# Main_Board_SW.net
KiCad netlist of a schematic drawn in EAGLE
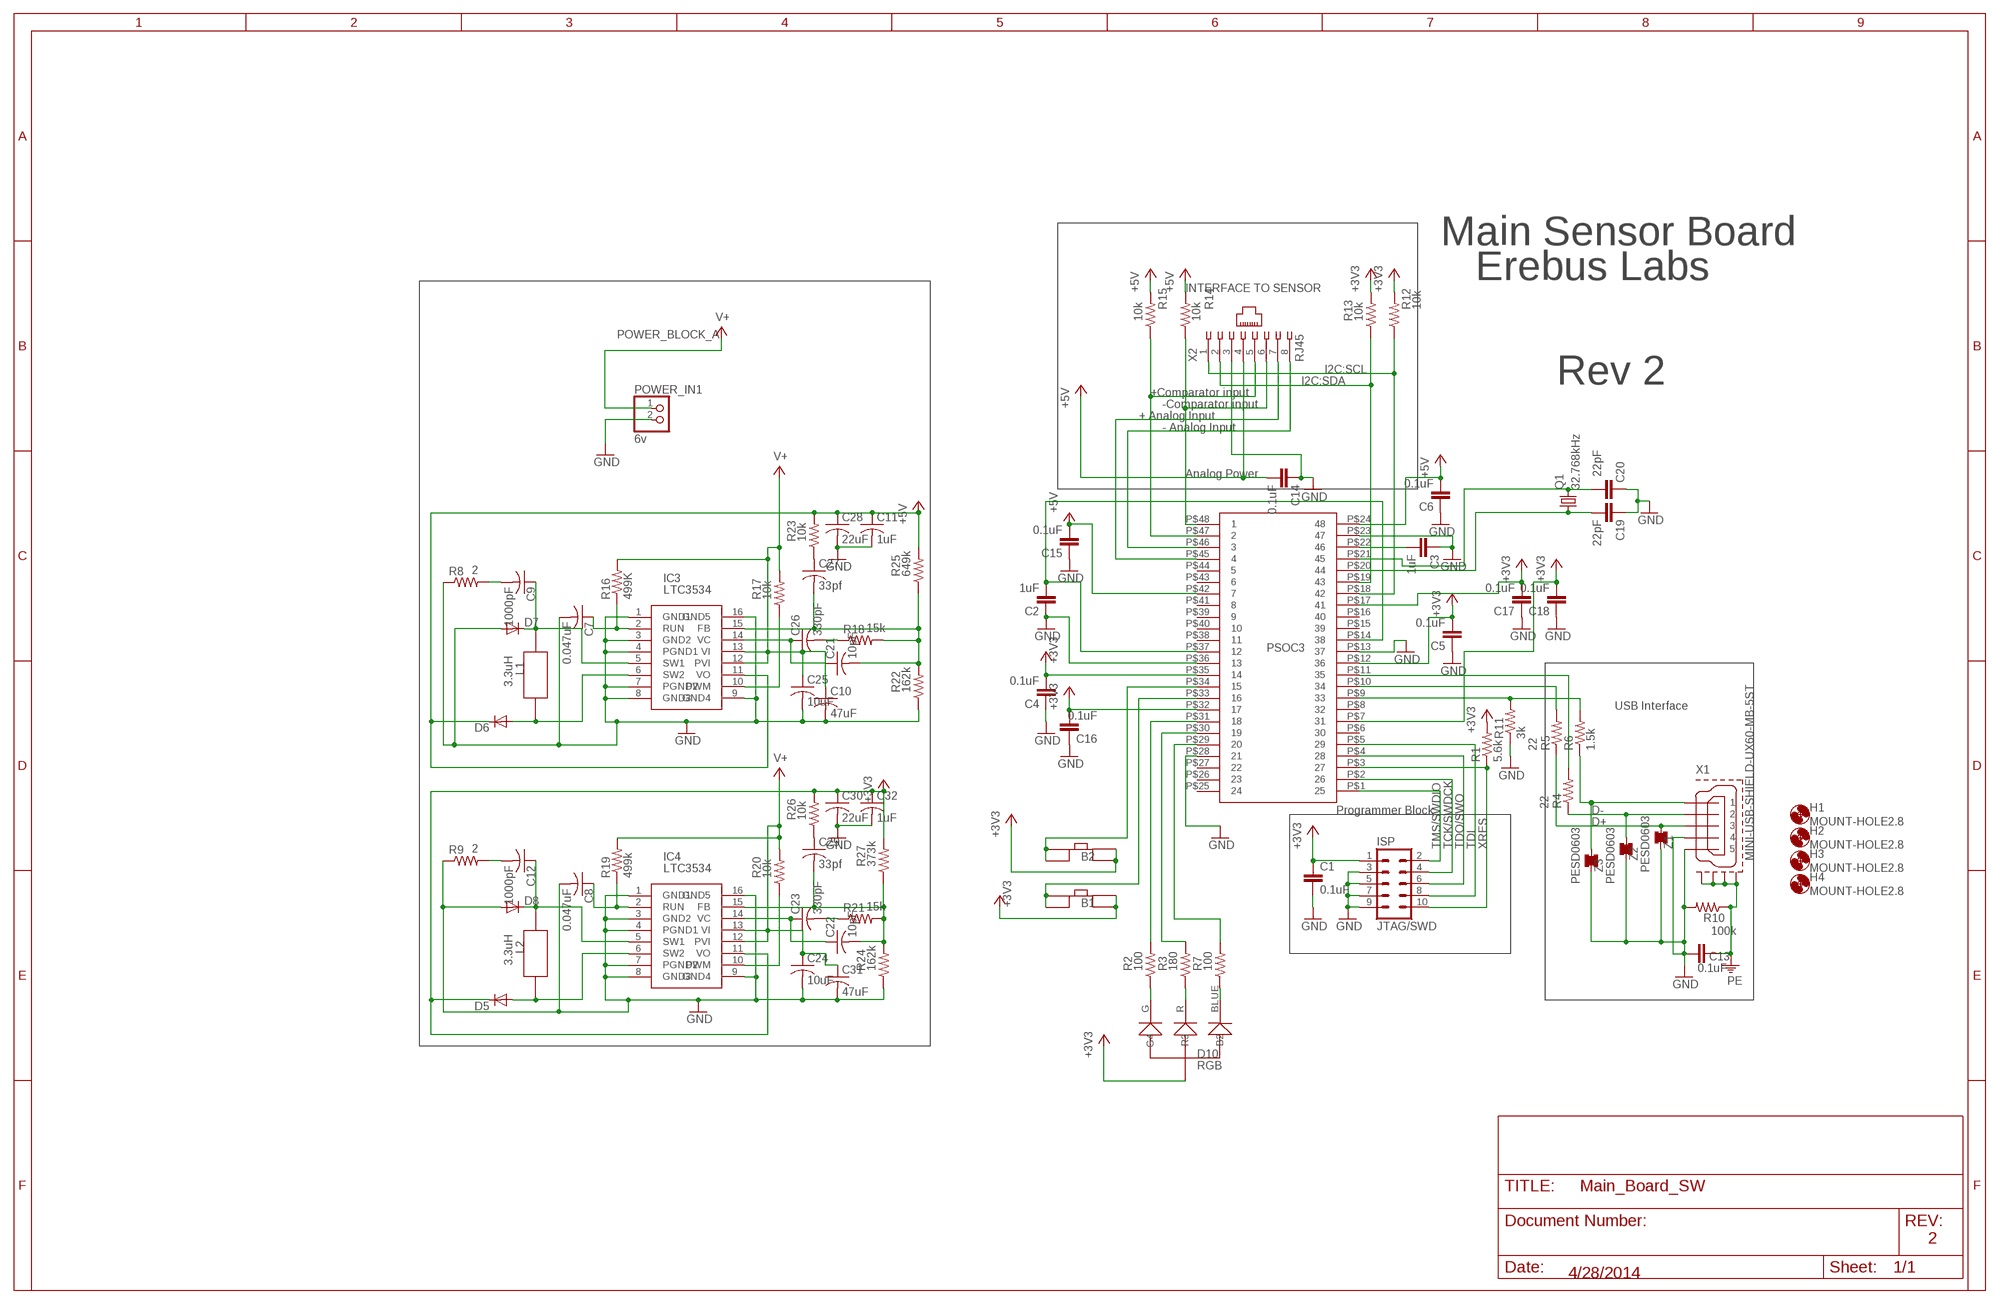
[diagram p0: schematic, sheet 1]

(export (version "E")
  (design (tool "Eeschema 10.0.6"))
  (components
    (comp (ref "C1")
      (value "0.1uF")
      (footprint "eagle-import:C0603K")
      (libsource (lib "eagle-import") (part "C-EUC0603K"))
    )
    (comp (ref "C2")
      (value "1uF")
      (footprint "eagle-import:C0603")
      (libsource (lib "eagle-import") (part "C-EUC0603"))
    )
    (comp (ref "C3")
      (value "1uF")
      (footprint "eagle-import:C0603")
      (libsource (lib "eagle-import") (part "C-EUC0603"))
    )
    (comp (ref "C4")
      (value "0.1uF")
      (footprint "eagle-import:C0603K")
      (libsource (lib "eagle-import") (part "C-EUC0603K"))
    )
    (comp (ref "C5")
      (value "0.1uF")
      (footprint "eagle-import:C0603K")
      (libsource (lib "eagle-import") (part "C-EUC0603K"))
    )
    (comp (ref "C6")
      (value "0.1uF")
      (footprint "eagle-import:C0603K")
      (libsource (lib "eagle-import") (part "C-EUC0603K"))
    )
    (comp (ref "C7")
      (value "0.047uF")
      (footprint "eagle-import:C0402")
      (libsource (lib "eagle-import") (part "C-USC0402"))
    )
    (comp (ref "C8")
      (value "0.047uF")
      (footprint "eagle-import:C0402")
      (libsource (lib "eagle-import") (part "C-USC0402"))
    )
    (comp (ref "C9")
      (value "1000pF")
      (footprint "eagle-import:C0402")
      (libsource (lib "eagle-import") (part "C-USC0402"))
    )
    (comp (ref "C10")
      (value "47uF")
      (footprint "eagle-import:C1210")
      (libsource (lib "eagle-import") (part "C-USC1210"))
    )
    (comp (ref "C11")
      (value "1uF")
      (footprint "eagle-import:C0603")
      (libsource (lib "eagle-import") (part "C-USC0603"))
    )
    (comp (ref "C12")
      (value "1000pF")
      (footprint "eagle-import:C0402")
      (libsource (lib "eagle-import") (part "C-USC0402"))
    )
    (comp (ref "C13")
      (value "0.1uF")
      (footprint "eagle-import:C0603K")
      (libsource (lib "eagle-import") (part "C-EUC0603K"))
    )
    (comp (ref "C14")
      (value "0.1uF")
      (footprint "eagle-import:C0603K")
      (libsource (lib "eagle-import") (part "C-EUC0603K"))
    )
    (comp (ref "C15")
      (value "0.1uF")
      (footprint "eagle-import:C0603K")
      (libsource (lib "eagle-import") (part "C-EUC0603K"))
    )
    (comp (ref "C16")
      (value "0.1uF")
      (footprint "eagle-import:C0603K")
      (libsource (lib "eagle-import") (part "C-EUC0603K"))
    )
    (comp (ref "C17")
      (value "0.1uF")
      (footprint "eagle-import:C0603K")
      (libsource (lib "eagle-import") (part "C-EUC0603K"))
    )
    (comp (ref "C18")
      (value "0.1uF")
      (footprint "eagle-import:C0603K")
      (libsource (lib "eagle-import") (part "C-EUC0603K"))
    )
    (comp (ref "C19")
      (value "22pF")
      (footprint "eagle-import:C0603")
      (libsource (lib "eagle-import") (part "C-EUC0603"))
    )
    (comp (ref "C20")
      (value "22pF")
      (footprint "eagle-import:C0603")
      (libsource (lib "eagle-import") (part "C-EUC0603"))
    )
    (comp (ref "C21")
      (value "10pF")
      (footprint "eagle-import:C0805")
      (libsource (lib "eagle-import") (part "C-USC0805"))
    )
    (comp (ref "C22")
      (value "10pF")
      (footprint "eagle-import:C0805")
      (libsource (lib "eagle-import") (part "C-USC0805"))
    )
    (comp (ref "C23")
      (value "330pF")
      (footprint "eagle-import:C0805")
      (libsource (lib "eagle-import") (part "C-USC0805"))
    )
    (comp (ref "C24")
      (value "10uF")
      (footprint "eagle-import:C0805")
      (libsource (lib "eagle-import") (part "C-USC0805"))
    )
    (comp (ref "C25")
      (value "10uF")
      (footprint "eagle-import:C0805")
      (libsource (lib "eagle-import") (part "C-USC0805"))
    )
    (comp (ref "C26")
      (value "330pF")
      (footprint "eagle-import:C0805")
      (libsource (lib "eagle-import") (part "C-USC0805"))
    )
    (comp (ref "C27")
      (value "33pf")
      (footprint "eagle-import:C0805")
      (libsource (lib "eagle-import") (part "C-USC0805"))
    )
    (comp (ref "C28")
      (value "22uF")
      (footprint "eagle-import:C0805")
      (libsource (lib "eagle-import") (part "C-USC0805"))
    )
    (comp (ref "C29")
      (value "33pf")
      (footprint "eagle-import:C0805")
      (libsource (lib "eagle-import") (part "C-USC0805"))
    )
    (comp (ref "C30")
      (value "22uF")
      (footprint "eagle-import:C0805")
      (libsource (lib "eagle-import") (part "C-USC0805"))
    )
    (comp (ref "C31")
      (value "47uF")
      (footprint "eagle-import:C1210")
      (libsource (lib "eagle-import") (part "C-USC1210"))
    )
    (comp (ref "C32")
      (value "1uF")
      (footprint "eagle-import:C0603")
      (libsource (lib "eagle-import") (part "C-USC0603"))
    )
    (comp (ref "D5")
      (value "DIODE-SOD323-R")
      (footprint "eagle-import:SOD323-R")
      (libsource (lib "eagle-import") (part "DIODE-SOD323-R"))
    )
    (comp (ref "D6")
      (value "DIODE-SOD323-R")
      (footprint "eagle-import:SOD323-R")
      (libsource (lib "eagle-import") (part "DIODE-SOD323-R"))
    )
    (comp (ref "D7")
      (value "DIODE-SOD323-R")
      (footprint "eagle-import:SOD323-R")
      (libsource (lib "eagle-import") (part "DIODE-SOD323-R"))
    )
    (comp (ref "D8")
      (value "DIODE-SOD323-R")
      (footprint "eagle-import:SOD323-R")
      (libsource (lib "eagle-import") (part "DIODE-SOD323-R"))
    )
    (comp (ref "H1")
      (value "MOUNT-HOLE2.8")
      (footprint "eagle-import:2,8")
      (libsource (lib "eagle-import") (part "MOUNT-HOLE2.8"))
    )
    (comp (ref "H2")
      (value "MOUNT-HOLE2.8")
      (footprint "eagle-import:2,8")
      (libsource (lib "eagle-import") (part "MOUNT-HOLE2.8"))
    )
    (comp (ref "H3")
      (value "MOUNT-HOLE2.8")
      (footprint "eagle-import:2,8")
      (libsource (lib "eagle-import") (part "MOUNT-HOLE2.8"))
    )
    (comp (ref "H4")
      (value "MOUNT-HOLE2.8")
      (footprint "eagle-import:2,8")
      (libsource (lib "eagle-import") (part "MOUNT-HOLE2.8"))
    )
    (comp (ref "ISP")
      (value "JTAG/SWD")
      (footprint "eagle-import:FTSH-105-01-L-DV-K")
      (libsource (lib "eagle-import") (part "FTSH-105-01-L-DV-K"))
    )
    (comp (ref "L1")
      (value "4.7uH")
      (footprint "eagle-import:SHEILDED_COIL")
      (libsource (lib "eagle-import") (part "SHEILDED_COIL"))
    )
    (comp (ref "L2")
      (value "4.7uH")
      (footprint "eagle-import:SHEILDED_COIL")
      (libsource (lib "eagle-import") (part "SHEILDED_COIL"))
    )
    (comp (ref "POWER_IN1")
      (value "6v")
      (footprint "eagle-import:1X02")
      (libsource (lib "eagle-import") (part "PINHD-1X2"))
    )
    (comp (ref "Q1")
      (value "32.768kHz")
      (footprint "eagle-import:TC38H")
      (libsource (lib "eagle-import") (part "CRYSTALTC38H"))
    )
    (comp (ref "R1")
      (value "5.6k")
      (footprint "eagle-import:R0805")
      (libsource (lib "eagle-import") (part "R-US_R0805"))
    )
    (comp (ref "R2")
      (value "100")
      (footprint "eagle-import:R0805")
      (libsource (lib "eagle-import") (part "R-US_R0805"))
    )
    (comp (ref "R3")
      (value "180")
      (footprint "eagle-import:R0805")
      (libsource (lib "eagle-import") (part "R-US_R0805"))
    )
    (comp (ref "R4")
      (value "22")
      (footprint "eagle-import:R0603")
      (libsource (lib "eagle-import") (part "R-US_R0603"))
    )
    (comp (ref "R5")
      (value "22")
      (footprint "eagle-import:R0603")
      (libsource (lib "eagle-import") (part "R-US_R0603"))
    )
    (comp (ref "R6")
      (value "1.5k")
      (footprint "eagle-import:R0805")
      (libsource (lib "eagle-import") (part "R-US_R0805"))
    )
    (comp (ref "R7")
      (value "100")
      (footprint "eagle-import:R0805")
      (libsource (lib "eagle-import") (part "R-US_R0805"))
    )
    (comp (ref "R8")
      (value "2")
      (footprint "eagle-import:R0402")
      (libsource (lib "eagle-import") (part "R-US_R0402"))
    )
    (comp (ref "R9")
      (value "2")
      (footprint "eagle-import:R0402")
      (libsource (lib "eagle-import") (part "R-US_R0402"))
    )
    (comp (ref "R10")
      (value "100k")
      (footprint "eagle-import:R0805")
      (libsource (lib "eagle-import") (part "R-US_R0805"))
    )
    (comp (ref "R11")
      (value "3k")
      (footprint "eagle-import:R0805")
      (libsource (lib "eagle-import") (part "R-US_R0805"))
    )
    (comp (ref "R12")
      (value "10k")
      (footprint "eagle-import:R0805")
      (libsource (lib "eagle-import") (part "R-US_R0805"))
    )
    (comp (ref "R13")
      (value "10k")
      (footprint "eagle-import:R0805")
      (libsource (lib "eagle-import") (part "R-US_R0805"))
    )
    (comp (ref "R14")
      (value "10k")
      (footprint "eagle-import:R0805")
      (libsource (lib "eagle-import") (part "R-US_R0805"))
    )
    (comp (ref "R15")
      (value "10k")
      (footprint "eagle-import:R0805")
      (libsource (lib "eagle-import") (part "R-US_R0805"))
    )
    (comp (ref "R16")
      (value "499K")
      (footprint "eagle-import:R1206")
      (libsource (lib "eagle-import") (part "resistor_R-US_R1206"))
    )
    (comp (ref "R17")
      (value "10k")
      (footprint "eagle-import:R0805")
      (libsource (lib "eagle-import") (part "R-US_R0805"))
    )
    (comp (ref "R18")
      (value "15k")
      (footprint "eagle-import:R0805")
      (libsource (lib "eagle-import") (part "R-US_R0805"))
    )
    (comp (ref "R19")
      (value "499k")
      (footprint "eagle-import:R1206")
      (libsource (lib "eagle-import") (part "resistor_R-US_R1206"))
    )
    (comp (ref "R20")
      (value "10k")
      (footprint "eagle-import:R0805")
      (libsource (lib "eagle-import") (part "R-US_R0805"))
    )
    (comp (ref "R21")
      (value "15k")
      (footprint "eagle-import:R0805")
      (libsource (lib "eagle-import") (part "R-US_R0805"))
    )
    (comp (ref "R22")
      (value "162k")
      (footprint "eagle-import:R0805")
      (libsource (lib "eagle-import") (part "R-US_R0805"))
    )
    (comp (ref "R23")
      (value "10k")
      (footprint "eagle-import:R0805")
      (libsource (lib "eagle-import") (part "R-US_R0805"))
    )
    (comp (ref "R24")
      (value "162k")
      (footprint "eagle-import:R0805")
      (libsource (lib "eagle-import") (part "R-US_R0805"))
    )
    (comp (ref "R25")
      (value "649k")
      (footprint "eagle-import:R0805")
      (libsource (lib "eagle-import") (part "R-US_R0805"))
    )
    (comp (ref "R26")
      (value "10k")
      (footprint "eagle-import:R0805")
      (libsource (lib "eagle-import") (part "R-US_R0805"))
    )
    (comp (ref "R27")
      (value "373k")
      (footprint "eagle-import:R0805")
      (libsource (lib "eagle-import") (part "R-US_R0805"))
    )
    (comp (ref "REGULATOR_3.3")
      (value "SWITCHER")
      (footprint "eagle-import:SSOP16")
      (libsource (lib "eagle-import") (part "SWITCHER"))
    )
    (comp (ref "REGULATOR_5")
      (value "SWITCHER")
      (footprint "eagle-import:SSOP16")
      (libsource (lib "eagle-import") (part "SWITCHER"))
    )
    (comp (ref "RGB_LED")
      (value "RGB_LED")
      (footprint "eagle-import:RGB_LED")
      (libsource (lib "eagle-import") (part "RGB_LED"))
    )
    (comp (ref "U$1")
      (value "PSOC_3_48PIN_SSOP")
      (footprint "eagle-import:PSOC_3_48PIN_SSOP")
      (libsource (lib "eagle-import") (part "PSOC_3_48PIN_SSOP"))
    )
    (comp (ref "U$5")
      (value "SPST")
      (footprint "eagle-import:SPST")
      (libsource (lib "eagle-import") (part "SPST"))
    )
    (comp (ref "U$6")
      (value "SPST")
      (footprint "eagle-import:SPST")
      (libsource (lib "eagle-import") (part "SPST"))
    )
    (comp (ref "X1")
      (value "MINI-USB-SHIELD-UX60-MB-5ST")
      (footprint "eagle-import:UX60-MB-5ST")
      (libsource (lib "eagle-import") (part "MINI-USB-SHIELD-UX60-MB-5ST"))
    )
    (comp (ref "X2")
      (value "RJ45")
      (footprint "eagle-import:555167-1")
      (libsource (lib "eagle-import") (part "555167-1"))
    )
    (comp (ref "Z1")
      (value "PESD0603")
      (footprint "eagle-import:SMD-0603")
      (libsource (lib "eagle-import") (part "PESD0603"))
    )
    (comp (ref "Z2")
      (value "PESD0603")
      (footprint "eagle-import:SMD-0603")
      (libsource (lib "eagle-import") (part "PESD0603"))
    )
    (comp (ref "Z3")
      (value "PESD0603")
      (footprint "eagle-import:SMD-0603")
      (libsource (lib "eagle-import") (part "PESD0603"))
    )
  )
  (nets
    (net (code "1") (name "+3V3") (class "Default")
      (node (ref "C1") (pin "1") (pinfunction "1_1") (pintype "passive"))
      (node (ref "C16") (pin "2") (pinfunction "2_2") (pintype "passive"))
      (node (ref "C17") (pin "2") (pinfunction "2_2") (pintype "passive"))
      (node (ref "C18") (pin "2") (pinfunction "2_2") (pintype "passive"))
      (node (ref "C30") (pin "1") (pinfunction "1_1") (pintype "passive"))
      (node (ref "C32") (pin "1") (pinfunction "1_1") (pintype "passive"))
      (node (ref "C4") (pin "2") (pinfunction "2_2") (pintype "passive"))
      (node (ref "C5") (pin "2") (pinfunction "2_2") (pintype "passive"))
      (node (ref "D5") (pin "C") (pinfunction "C_C") (pintype "passive"))
      (node (ref "ISP") (pin "1") (pinfunction "1_1") (pintype "passive"))
      (node (ref "R1") (pin "2") (pinfunction "2_2") (pintype "passive"))
      (node (ref "R12") (pin "2") (pinfunction "2_2") (pintype "passive"))
      (node (ref "R13") (pin "2") (pinfunction "2_2") (pintype "passive"))
      (node (ref "R26") (pin "2") (pinfunction "2_2") (pintype "passive"))
      (node (ref "R27") (pin "2") (pinfunction "2_2") (pintype "passive"))
      (node (ref "REGULATOR_3.3") (pin "11") (pinfunction "VO_11") (pintype "bidirectional"))
      (node (ref "RGB_LED") (pin "VCC") (pinfunction "VCC1_VCC") (pintype "bidirectional"))
      (node (ref "U$1") (pin "P$12") (pinfunction "36_P$12") (pintype "bidirectional"))
      (node (ref "U$1") (pin "P$17") (pinfunction "41_P$17") (pintype "bidirectional"))
      (node (ref "U$1") (pin "P$32") (pinfunction "17_P$32") (pintype "bidirectional"))
      (node (ref "U$1") (pin "P$35") (pinfunction "14_P$35") (pintype "bidirectional"))
      (node (ref "U$1") (pin "P$7") (pinfunction "31_P$7") (pintype "bidirectional"))
      (node (ref "U$5") (pin "B1") (pinfunction "B1_B1") (pintype "bidirectional"))
      (node (ref "U$5") (pin "B2") (pinfunction "B2_B2") (pintype "bidirectional"))
      (node (ref "U$6") (pin "B1") (pinfunction "B1_B1") (pintype "bidirectional"))
      (node (ref "U$6") (pin "B2") (pinfunction "B2_B2") (pintype "bidirectional"))
    )
    (net (code "2") (name "+5V") (class "Default")
      (node (ref "C11") (pin "1") (pinfunction "1_1") (pintype "passive"))
      (node (ref "C14") (pin "2") (pinfunction "2_2") (pintype "passive"))
      (node (ref "C15") (pin "2") (pinfunction "2_2") (pintype "passive"))
      (node (ref "C28") (pin "1") (pinfunction "1_1") (pintype "passive"))
      (node (ref "C6") (pin "2") (pinfunction "2_2") (pintype "passive"))
      (node (ref "D6") (pin "C") (pinfunction "C_C") (pintype "passive"))
      (node (ref "R14") (pin "2") (pinfunction "2_2") (pintype "passive"))
      (node (ref "R15") (pin "2") (pinfunction "2_2") (pintype "passive"))
      (node (ref "R23") (pin "2") (pinfunction "2_2") (pintype "passive"))
      (node (ref "R25") (pin "2") (pinfunction "2_2") (pintype "passive"))
      (node (ref "REGULATOR_5") (pin "11") (pinfunction "VO_11") (pintype "bidirectional"))
      (node (ref "U$1") (pin "P$24") (pinfunction "48_P$24") (pintype "bidirectional"))
      (node (ref "U$1") (pin "P$42") (pinfunction "7_P$42") (pintype "bidirectional"))
      (node (ref "X2") (pin "4") (pinfunction "4_4") (pintype "passive"))
    )
    (net (code "3") (name "GND") (class "Default")
      (node (ref "C1") (pin "2") (pinfunction "2_2") (pintype "passive"))
      (node (ref "C10") (pin "2") (pinfunction "2_2") (pintype "passive"))
      (node (ref "C11") (pin "2") (pinfunction "2_2") (pintype "passive"))
      (node (ref "C13") (pin "2") (pinfunction "2_2") (pintype "passive"))
      (node (ref "C14") (pin "1") (pinfunction "1_1") (pintype "passive"))
      (node (ref "C15") (pin "1") (pinfunction "1_1") (pintype "passive"))
      (node (ref "C16") (pin "1") (pinfunction "1_1") (pintype "passive"))
      (node (ref "C17") (pin "1") (pinfunction "1_1") (pintype "passive"))
      (node (ref "C18") (pin "1") (pinfunction "1_1") (pintype "passive"))
      (node (ref "C19") (pin "1") (pinfunction "1_1") (pintype "passive"))
      (node (ref "C2") (pin "1") (pinfunction "1_1") (pintype "passive"))
      (node (ref "C20") (pin "1") (pinfunction "1_1") (pintype "passive"))
      (node (ref "C24") (pin "2") (pinfunction "2_2") (pintype "passive"))
      (node (ref "C25") (pin "2") (pinfunction "2_2") (pintype "passive"))
      (node (ref "C28") (pin "2") (pinfunction "2_2") (pintype "passive"))
      (node (ref "C3") (pin "1") (pinfunction "1_1") (pintype "passive"))
      (node (ref "C30") (pin "2") (pinfunction "2_2") (pintype "passive"))
      (node (ref "C31") (pin "2") (pinfunction "2_2") (pintype "passive"))
      (node (ref "C32") (pin "2") (pinfunction "2_2") (pintype "passive"))
      (node (ref "C4") (pin "1") (pinfunction "1_1") (pintype "passive"))
      (node (ref "C5") (pin "1") (pinfunction "1_1") (pintype "passive"))
      (node (ref "C6") (pin "1") (pinfunction "1_1") (pintype "passive"))
      (node (ref "C7") (pin "2") (pinfunction "2_2") (pintype "passive"))
      (node (ref "C8") (pin "2") (pinfunction "2_2") (pintype "passive"))
      (node (ref "D7") (pin "A") (pinfunction "A_A") (pintype "passive"))
      (node (ref "D8") (pin "A") (pinfunction "A_A") (pintype "passive"))
      (node (ref "ISP") (pin "3") (pinfunction "3_3") (pintype "passive"))
      (node (ref "ISP") (pin "5") (pinfunction "5_5") (pintype "passive"))
      (node (ref "ISP") (pin "7") (pinfunction "7_7") (pintype "passive"))
      (node (ref "ISP") (pin "9") (pinfunction "9_9") (pintype "passive"))
      (node (ref "POWER_IN1") (pin "2") (pinfunction "2_2") (pintype "passive"))
      (node (ref "R10") (pin "2") (pinfunction "2_2") (pintype "passive"))
      (node (ref "R11") (pin "1") (pinfunction "1_1") (pintype "passive"))
      (node (ref "R22") (pin "1") (pinfunction "1_1") (pintype "passive"))
      (node (ref "R24") (pin "1") (pinfunction "1_1") (pintype "passive"))
      (node (ref "R8") (pin "1") (pinfunction "1_1") (pintype "passive"))
      (node (ref "R9") (pin "1") (pinfunction "1_1") (pintype "passive"))
      (node (ref "REGULATOR_3.3") (pin "1") (pinfunction "GND1_1") (pintype "bidirectional"))
      (node (ref "REGULATOR_3.3") (pin "16") (pinfunction "GND5_16") (pintype "bidirectional"))
      (node (ref "REGULATOR_3.3") (pin "3") (pinfunction "GND2_3") (pintype "bidirectional"))
      (node (ref "REGULATOR_3.3") (pin "4") (pinfunction "PGND1_4") (pintype "bidirectional"))
      (node (ref "REGULATOR_3.3") (pin "7") (pinfunction "PGND2_7") (pintype "bidirectional"))
      (node (ref "REGULATOR_3.3") (pin "8") (pinfunction "GND3_8") (pintype "bidirectional"))
      (node (ref "REGULATOR_3.3") (pin "9") (pinfunction "GND4_9") (pintype "bidirectional"))
      (node (ref "REGULATOR_5") (pin "1") (pinfunction "GND1_1") (pintype "bidirectional"))
      (node (ref "REGULATOR_5") (pin "16") (pinfunction "GND5_16") (pintype "bidirectional"))
      (node (ref "REGULATOR_5") (pin "3") (pinfunction "GND2_3") (pintype "bidirectional"))
      (node (ref "REGULATOR_5") (pin "4") (pinfunction "PGND1_4") (pintype "bidirectional"))
      (node (ref "REGULATOR_5") (pin "7") (pinfunction "PGND2_7") (pintype "bidirectional"))
      (node (ref "REGULATOR_5") (pin "8") (pinfunction "GND3_8") (pintype "bidirectional"))
      (node (ref "REGULATOR_5") (pin "9") (pinfunction "GND4_9") (pintype "bidirectional"))
      (node (ref "U$1") (pin "P$13") (pinfunction "37_P$13") (pintype "bidirectional"))
      (node (ref "U$1") (pin "P$23") (pinfunction "47_P$23") (pintype "bidirectional"))
      (node (ref "U$1") (pin "P$28") (pinfunction "21_P$28") (pintype "bidirectional"))
      (node (ref "U$1") (pin "P$36") (pinfunction "13_P$36") (pintype "bidirectional"))
      (node (ref "X1") (pin "4") (pinfunction "4_4") (pintype "input"))
      (node (ref "X1") (pin "5") (pinfunction "5_5") (pintype "input"))
      (node (ref "X2") (pin "3") (pinfunction "3_3") (pintype "passive"))
      (node (ref "Z1") (pin "1") (pinfunction "1_1") (pintype "passive"))
      (node (ref "Z2") (pin "1") (pinfunction "1_1") (pintype "passive"))
      (node (ref "Z3") (pin "1") (pinfunction "1_1") (pintype "passive"))
    )
    (net (code "4") (name "Net-(C9-Pad2)") (class "Default")
      (node (ref "C9") (pin "2") (pinfunction "2_2") (pintype "passive"))
      (node (ref "R8") (pin "2") (pinfunction "2_2") (pintype "passive"))
    )
    (net (code "5") (name "Net-(C12-Pad2)") (class "Default")
      (node (ref "C12") (pin "2") (pinfunction "2_2") (pintype "passive"))
      (node (ref "R9") (pin "2") (pinfunction "2_2") (pintype "passive"))
    )
    (net (code "6") (name "Net-(C23-Pad2)") (class "Default")
      (node (ref "C23") (pin "2") (pinfunction "2_2") (pintype "passive"))
      (node (ref "R21") (pin "1") (pinfunction "1_1") (pintype "passive"))
    )
    (net (code "7") (name "Net-(C26-Pad2)") (class "Default")
      (node (ref "C26") (pin "2") (pinfunction "2_2") (pintype "passive"))
      (node (ref "R18") (pin "1") (pinfunction "1_1") (pintype "passive"))
    )
    (net (code "8") (name "Net-(C27-Pad1)") (class "Default")
      (node (ref "C27") (pin "1") (pinfunction "1_1") (pintype "passive"))
      (node (ref "R23") (pin "1") (pinfunction "1_1") (pintype "passive"))
    )
    (net (code "9") (name "Net-(C29-Pad1)") (class "Default")
      (node (ref "C29") (pin "1") (pinfunction "1_1") (pintype "passive"))
      (node (ref "R26") (pin "1") (pinfunction "1_1") (pintype "passive"))
    )
    (net (code "10") (name "Net-(R4-Pad1)") (class "Default")
      (node (ref "R4") (pin "1") (pinfunction "1_1") (pintype "passive"))
      (node (ref "X1") (pin "2") (pinfunction "2_2") (pintype "input"))
      (node (ref "Z2") (pin "2") (pinfunction "2_2") (pintype "passive"))
    )
    (net (code "11") (name "Net-(R5-Pad1)") (class "Default")
      (node (ref "R5") (pin "1") (pinfunction "1_1") (pintype "passive"))
      (node (ref "X1") (pin "3") (pinfunction "3_3") (pintype "input"))
      (node (ref "Z1") (pin "2") (pinfunction "2_2") (pintype "passive"))
    )
    (net (code "12") (name "Net-(R6-Pad1)") (class "Default")
      (node (ref "R6") (pin "1") (pinfunction "1_1") (pintype "passive"))
      (node (ref "X1") (pin "1") (pinfunction "1_1") (pintype "input"))
      (node (ref "Z3") (pin "2") (pinfunction "2_2") (pintype "passive"))
    )
    (net (code "13") (name "Net-(REGULATOR_3.3-FB)") (class "Default")
      (node (ref "C22") (pin "2") (pinfunction "2_2") (pintype "passive"))
      (node (ref "C29") (pin "2") (pinfunction "2_2") (pintype "passive"))
      (node (ref "R21") (pin "2") (pinfunction "2_2") (pintype "passive"))
      (node (ref "R24") (pin "2") (pinfunction "2_2") (pintype "passive"))
      (node (ref "R27") (pin "1") (pinfunction "1_1") (pintype "passive"))
      (node (ref "REGULATOR_3.3") (pin "15") (pinfunction "FB_15") (pintype "bidirectional"))
    )
    (net (code "14") (name "Net-(REGULATOR_3.3-PWM)") (class "Default")
      (node (ref "R20") (pin "1") (pinfunction "1_1") (pintype "passive"))
      (node (ref "REGULATOR_3.3") (pin "10") (pinfunction "PWM_10") (pintype "bidirectional"))
    )
    (net (code "15") (name "Net-(REGULATOR_3.3-RUN)") (class "Default")
      (node (ref "C8") (pin "1") (pinfunction "1_1") (pintype "passive"))
      (node (ref "R19") (pin "1") (pinfunction "1_1") (pintype "passive"))
      (node (ref "REGULATOR_3.3") (pin "2") (pinfunction "RUN_2") (pintype "bidirectional"))
    )
    (net (code "16") (name "Net-(REGULATOR_3.3-SW1)") (class "Default")
      (node (ref "C12") (pin "1") (pinfunction "1_1") (pintype "passive"))
      (node (ref "D8") (pin "C") (pinfunction "C_C") (pintype "passive"))
      (node (ref "L2") (pin "P$2") (pinfunction "P$2_P$2") (pintype "bidirectional"))
      (node (ref "REGULATOR_3.3") (pin "5") (pinfunction "SW1_5") (pintype "bidirectional"))
    )
    (net (code "17") (name "Net-(REGULATOR_3.3-SW2)") (class "Default")
      (node (ref "D5") (pin "A") (pinfunction "A_A") (pintype "passive"))
      (node (ref "L2") (pin "P$1") (pinfunction "P$1_P$1") (pintype "bidirectional"))
      (node (ref "REGULATOR_3.3") (pin "6") (pinfunction "SW2_6") (pintype "bidirectional"))
    )
    (net (code "18") (name "Net-(REGULATOR_3.3-VC)") (class "Default")
      (node (ref "C22") (pin "1") (pinfunction "1_1") (pintype "passive"))
      (node (ref "C23") (pin "1") (pinfunction "1_1") (pintype "passive"))
      (node (ref "REGULATOR_3.3") (pin "14") (pinfunction "VC_14") (pintype "bidirectional"))
    )
    (net (code "19") (name "Net-(REGULATOR_5-FB)") (class "Default")
      (node (ref "C21") (pin "2") (pinfunction "2_2") (pintype "passive"))
      (node (ref "C27") (pin "2") (pinfunction "2_2") (pintype "passive"))
      (node (ref "R18") (pin "2") (pinfunction "2_2") (pintype "passive"))
      (node (ref "R22") (pin "2") (pinfunction "2_2") (pintype "passive"))
      (node (ref "R25") (pin "1") (pinfunction "1_1") (pintype "passive"))
      (node (ref "REGULATOR_5") (pin "15") (pinfunction "FB_15") (pintype "bidirectional"))
    )
    (net (code "20") (name "Net-(REGULATOR_5-PWM)") (class "Default")
      (node (ref "R17") (pin "1") (pinfunction "1_1") (pintype "passive"))
      (node (ref "REGULATOR_5") (pin "10") (pinfunction "PWM_10") (pintype "bidirectional"))
    )
    (net (code "21") (name "Net-(REGULATOR_5-RUN)") (class "Default")
      (node (ref "C7") (pin "1") (pinfunction "1_1") (pintype "passive"))
      (node (ref "R16") (pin "1") (pinfunction "1_1") (pintype "passive"))
      (node (ref "REGULATOR_5") (pin "2") (pinfunction "RUN_2") (pintype "bidirectional"))
    )
    (net (code "22") (name "Net-(REGULATOR_5-SW1)") (class "Default")
      (node (ref "C9") (pin "1") (pinfunction "1_1") (pintype "passive"))
      (node (ref "D7") (pin "C") (pinfunction "C_C") (pintype "passive"))
      (node (ref "L1") (pin "P$2") (pinfunction "P$2_P$2") (pintype "bidirectional"))
      (node (ref "REGULATOR_5") (pin "5") (pinfunction "SW1_5") (pintype "bidirectional"))
    )
    (net (code "23") (name "Net-(REGULATOR_5-SW2)") (class "Default")
      (node (ref "D6") (pin "A") (pinfunction "A_A") (pintype "passive"))
      (node (ref "L1") (pin "P$1") (pinfunction "P$1_P$1") (pintype "bidirectional"))
      (node (ref "REGULATOR_5") (pin "6") (pinfunction "SW2_6") (pintype "bidirectional"))
    )
    (net (code "24") (name "Net-(REGULATOR_5-VC)") (class "Default")
      (node (ref "C21") (pin "1") (pinfunction "1_1") (pintype "passive"))
      (node (ref "C26") (pin "1") (pinfunction "1_1") (pintype "passive"))
      (node (ref "REGULATOR_5") (pin "14") (pinfunction "VC_14") (pintype "bidirectional"))
    )
    (net (code "25") (name "Net-(RGB_LED-B2)") (class "Default")
      (node (ref "R7") (pin "1") (pinfunction "1_1") (pintype "passive"))
      (node (ref "RGB_LED") (pin "BLUE") (pinfunction "B2_BLUE") (pintype "bidirectional"))
    )
    (net (code "26") (name "Net-(RGB_LED-G4)") (class "Default")
      (node (ref "R2") (pin "1") (pinfunction "1_1") (pintype "passive"))
      (node (ref "RGB_LED") (pin "G") (pinfunction "G4_G") (pintype "bidirectional"))
    )
    (net (code "27") (name "Net-(RGB_LED-R3)") (class "Default")
      (node (ref "R3") (pin "1") (pinfunction "1_1") (pintype "passive"))
      (node (ref "RGB_LED") (pin "R") (pinfunction "R3_R") (pintype "bidirectional"))
    )
    (net (code "28") (name "Net-(U$1-1)") (class "Default")
      (node (ref "R14") (pin "1") (pinfunction "1_1") (pintype "passive"))
      (node (ref "U$1") (pin "P$48") (pinfunction "1_P$48") (pintype "bidirectional"))
      (node (ref "X2") (pin "6") (pinfunction "6_6") (pintype "passive"))
    )
    (net (code "29") (name "Net-(U$1-2)") (class "Default")
      (node (ref "R15") (pin "1") (pinfunction "1_1") (pintype "passive"))
      (node (ref "U$1") (pin "P$47") (pinfunction "2_P$47") (pintype "bidirectional"))
      (node (ref "X2") (pin "5") (pinfunction "5_5") (pintype "passive"))
    )
    (net (code "30") (name "Net-(U$1-3)") (class "Default")
      (node (ref "U$1") (pin "P$46") (pinfunction "3_P$46") (pintype "bidirectional"))
      (node (ref "X2") (pin "8") (pinfunction "8_8") (pintype "passive"))
    )
    (net (code "31") (name "Net-(U$1-4)") (class "Default")
      (node (ref "U$1") (pin "P$45") (pinfunction "4_P$45") (pintype "bidirectional"))
      (node (ref "X2") (pin "7") (pinfunction "7_7") (pintype "passive"))
    )
    (net (code "32") (name "Net-(U$1-12)") (class "Default")
      (node (ref "C2") (pin "2") (pinfunction "2_2") (pintype "passive"))
      (node (ref "U$1") (pin "P$14") (pinfunction "38_P$14") (pintype "bidirectional"))
      (node (ref "U$1") (pin "P$37") (pinfunction "12_P$37") (pintype "bidirectional"))
    )
    (net (code "33") (name "Net-(U$1-15)") (class "Default")
      (node (ref "U$1") (pin "P$34") (pinfunction "15_P$34") (pintype "bidirectional"))
      (node (ref "U$5") (pin "A1") (pinfunction "A1_A1") (pintype "bidirectional"))
      (node (ref "U$5") (pin "A2") (pinfunction "A2_A2") (pintype "bidirectional"))
    )
    (net (code "34") (name "Net-(U$1-16)") (class "Default")
      (node (ref "U$1") (pin "P$33") (pinfunction "16_P$33") (pintype "bidirectional"))
      (node (ref "U$6") (pin "A1") (pinfunction "A1_A1") (pintype "bidirectional"))
      (node (ref "U$6") (pin "A2") (pinfunction "A2_A2") (pintype "bidirectional"))
    )
    (net (code "35") (name "Net-(U$1-18)") (class "Default")
      (node (ref "R2") (pin "2") (pinfunction "2_2") (pintype "passive"))
      (node (ref "U$1") (pin "P$31") (pinfunction "18_P$31") (pintype "bidirectional"))
    )
    (net (code "36") (name "Net-(U$1-19)") (class "Default")
      (node (ref "R3") (pin "2") (pinfunction "2_2") (pintype "passive"))
      (node (ref "U$1") (pin "P$30") (pinfunction "19_P$30") (pintype "bidirectional"))
    )
    (net (code "37") (name "Net-(U$1-20)") (class "Default")
      (node (ref "R7") (pin "2") (pinfunction "2_2") (pintype "passive"))
      (node (ref "U$1") (pin "P$29") (pinfunction "20_P$29") (pintype "bidirectional"))
    )
    (net (code "38") (name "Net-(U$1-25)") (class "Default")
      (node (ref "ISP") (pin "2") (pinfunction "2_2") (pintype "passive"))
      (node (ref "U$1") (pin "P$1") (pinfunction "25_P$1") (pintype "bidirectional"))
    )
    (net (code "39") (name "Net-(U$1-26)") (class "Default")
      (node (ref "ISP") (pin "4") (pinfunction "4_4") (pintype "passive"))
      (node (ref "U$1") (pin "P$2") (pinfunction "26_P$2") (pintype "bidirectional"))
    )
    (net (code "40") (name "Net-(U$1-27)") (class "Default")
      (node (ref "ISP") (pin "10") (pinfunction "10_10") (pintype "passive"))
      (node (ref "R1") (pin "1") (pinfunction "1_1") (pintype "passive"))
      (node (ref "U$1") (pin "P$3") (pinfunction "27_P$3") (pintype "bidirectional"))
    )
    (net (code "41") (name "Net-(U$1-28)") (class "Default")
      (node (ref "ISP") (pin "6") (pinfunction "6_6") (pintype "passive"))
      (node (ref "U$1") (pin "P$4") (pinfunction "28_P$4") (pintype "bidirectional"))
    )
    (net (code "42") (name "Net-(U$1-29)") (class "Default")
      (node (ref "ISP") (pin "8") (pinfunction "8_8") (pintype "passive"))
      (node (ref "U$1") (pin "P$5") (pinfunction "29_P$5") (pintype "bidirectional"))
    )
    (net (code "43") (name "Net-(U$1-33)") (class "Default")
      (node (ref "R11") (pin "2") (pinfunction "2_2") (pintype "passive"))
      (node (ref "R6") (pin "2") (pinfunction "2_2") (pintype "passive"))
      (node (ref "U$1") (pin "P$9") (pinfunction "33_P$9") (pintype "bidirectional"))
    )
    (net (code "44") (name "Net-(U$1-34)") (class "Default")
      (node (ref "R5") (pin "2") (pinfunction "2_2") (pintype "passive"))
      (node (ref "U$1") (pin "P$10") (pinfunction "34_P$10") (pintype "bidirectional"))
    )
    (net (code "45") (name "Net-(U$1-35)") (class "Default")
      (node (ref "R4") (pin "2") (pinfunction "2_2") (pintype "passive"))
      (node (ref "U$1") (pin "P$11") (pinfunction "35_P$11") (pintype "bidirectional"))
    )
    (net (code "46") (name "Net-(U$1-42)") (class "Default")
      (node (ref "R12") (pin "1") (pinfunction "1_1") (pintype "passive"))
      (node (ref "U$1") (pin "P$18") (pinfunction "42_P$18") (pintype "bidirectional"))
      (node (ref "X2") (pin "1") (pinfunction "1_1") (pintype "passive"))
    )
    (net (code "47") (name "Net-(U$1-43)") (class "Default")
      (node (ref "R13") (pin "1") (pinfunction "1_1") (pintype "passive"))
      (node (ref "U$1") (pin "P$19") (pinfunction "43_P$19") (pintype "bidirectional"))
      (node (ref "X2") (pin "2") (pinfunction "2_2") (pintype "passive"))
    )
    (net (code "48") (name "Net-(U$1-44)") (class "Default")
      (node (ref "C19") (pin "2") (pinfunction "2_2") (pintype "passive"))
      (node (ref "Q1") (pin "1") (pinfunction "1_1") (pintype "passive"))
      (node (ref "U$1") (pin "P$20") (pinfunction "44_P$20") (pintype "bidirectional"))
    )
    (net (code "49") (name "Net-(U$1-45)") (class "Default")
      (node (ref "C20") (pin "2") (pinfunction "2_2") (pintype "passive"))
      (node (ref "Q1") (pin "2") (pinfunction "2_2") (pintype "passive"))
      (node (ref "U$1") (pin "P$21") (pinfunction "45_P$21") (pintype "bidirectional"))
    )
    (net (code "50") (name "Net-(U$1-46)") (class "Default")
      (node (ref "C3") (pin "2") (pinfunction "2_2") (pintype "passive"))
      (node (ref "U$1") (pin "P$22") (pinfunction "46_P$22") (pintype "bidirectional"))
    )
    (net (code "51") (name "PE") (class "Default")
      (node (ref "C13") (pin "1") (pinfunction "1_1") (pintype "passive"))
      (node (ref "R10") (pin "1") (pinfunction "1_1") (pintype "passive"))
      (node (ref "X1") (pin "M1") (pinfunction "GND1_M1") (pintype "bidirectional"))
      (node (ref "X1") (pin "M2") (pinfunction "GND2_M2") (pintype "bidirectional"))
      (node (ref "X1") (pin "M3") (pinfunction "GND3_M3") (pintype "bidirectional"))
      (node (ref "X1") (pin "M4") (pinfunction "GND4_M4") (pintype "bidirectional"))
    )
    (net (code "52") (name "V+") (class "Default")
      (node (ref "C10") (pin "1") (pinfunction "1_1") (pintype "passive"))
      (node (ref "C24") (pin "1") (pinfunction "1_1") (pintype "passive"))
      (node (ref "C25") (pin "1") (pinfunction "1_1") (pintype "passive"))
      (node (ref "C31") (pin "1") (pinfunction "1_1") (pintype "passive"))
      (node (ref "POWER_IN1") (pin "1") (pinfunction "1_1") (pintype "passive"))
      (node (ref "R16") (pin "2") (pinfunction "2_2") (pintype "passive"))
      (node (ref "R17") (pin "2") (pinfunction "2_2") (pintype "passive"))
      (node (ref "R19") (pin "2") (pinfunction "2_2") (pintype "passive"))
      (node (ref "R20") (pin "2") (pinfunction "2_2") (pintype "passive"))
      (node (ref "REGULATOR_3.3") (pin "12") (pinfunction "PVI_12") (pintype "bidirectional"))
      (node (ref "REGULATOR_3.3") (pin "13") (pinfunction "VI_13") (pintype "bidirectional"))
      (node (ref "REGULATOR_5") (pin "12") (pinfunction "PVI_12") (pintype "bidirectional"))
      (node (ref "REGULATOR_5") (pin "13") (pinfunction "VI_13") (pintype "bidirectional"))
    )
    (net (code "53") (name "unconnected-(U$1-5-PadP$44)") (class "Default")
      (node (ref "U$1") (pin "P$44") (pinfunction "5_P$44") (pintype "bidirectional"))
    )
    (net (code "54") (name "unconnected-(U$1-6-PadP$43)") (class "Default")
      (node (ref "U$1") (pin "P$43") (pinfunction "6_P$43") (pintype "bidirectional"))
    )
    (net (code "55") (name "unconnected-(U$1-8-PadP$41)") (class "Default")
      (node (ref "U$1") (pin "P$41") (pinfunction "8_P$41") (pintype "bidirectional"))
    )
    (net (code "56") (name "unconnected-(U$1-9-PadP$39)") (class "Default")
      (node (ref "U$1") (pin "P$39") (pinfunction "9_P$39") (pintype "bidirectional"))
    )
    (net (code "57") (name "unconnected-(U$1-10-PadP$40)") (class "Default")
      (node (ref "U$1") (pin "P$40") (pinfunction "10_P$40") (pintype "bidirectional"))
    )
    (net (code "58") (name "unconnected-(U$1-11-PadP$38)") (class "Default")
      (node (ref "U$1") (pin "P$38") (pinfunction "11_P$38") (pintype "bidirectional"))
    )
    (net (code "59") (name "unconnected-(U$1-22-PadP$27)") (class "Default")
      (node (ref "U$1") (pin "P$27") (pinfunction "22_P$27") (pintype "bidirectional"))
    )
    (net (code "60") (name "unconnected-(U$1-23-PadP$26)") (class "Default")
      (node (ref "U$1") (pin "P$26") (pinfunction "23_P$26") (pintype "bidirectional"))
    )
    (net (code "61") (name "unconnected-(U$1-24-PadP$25)") (class "Default")
      (node (ref "U$1") (pin "P$25") (pinfunction "24_P$25") (pintype "bidirectional"))
    )
    (net (code "62") (name "unconnected-(U$1-30-PadP$6)") (class "Default")
      (node (ref "U$1") (pin "P$6") (pinfunction "30_P$6") (pintype "bidirectional"))
    )
    (net (code "63") (name "unconnected-(U$1-32-PadP$8)") (class "Default")
      (node (ref "U$1") (pin "P$8") (pinfunction "32_P$8") (pintype "bidirectional"))
    )
    (net (code "64") (name "unconnected-(U$1-39-PadP$15)") (class "Default")
      (node (ref "U$1") (pin "P$15") (pinfunction "39_P$15") (pintype "bidirectional"))
    )
    (net (code "65") (name "unconnected-(U$1-40-PadP$16)") (class "Default")
      (node (ref "U$1") (pin "P$16") (pinfunction "40_P$16") (pintype "bidirectional"))
    )
  )
)
